# TeraDMX_v1_2.net
KiCad netlist of a schematic drawn in EAGLE
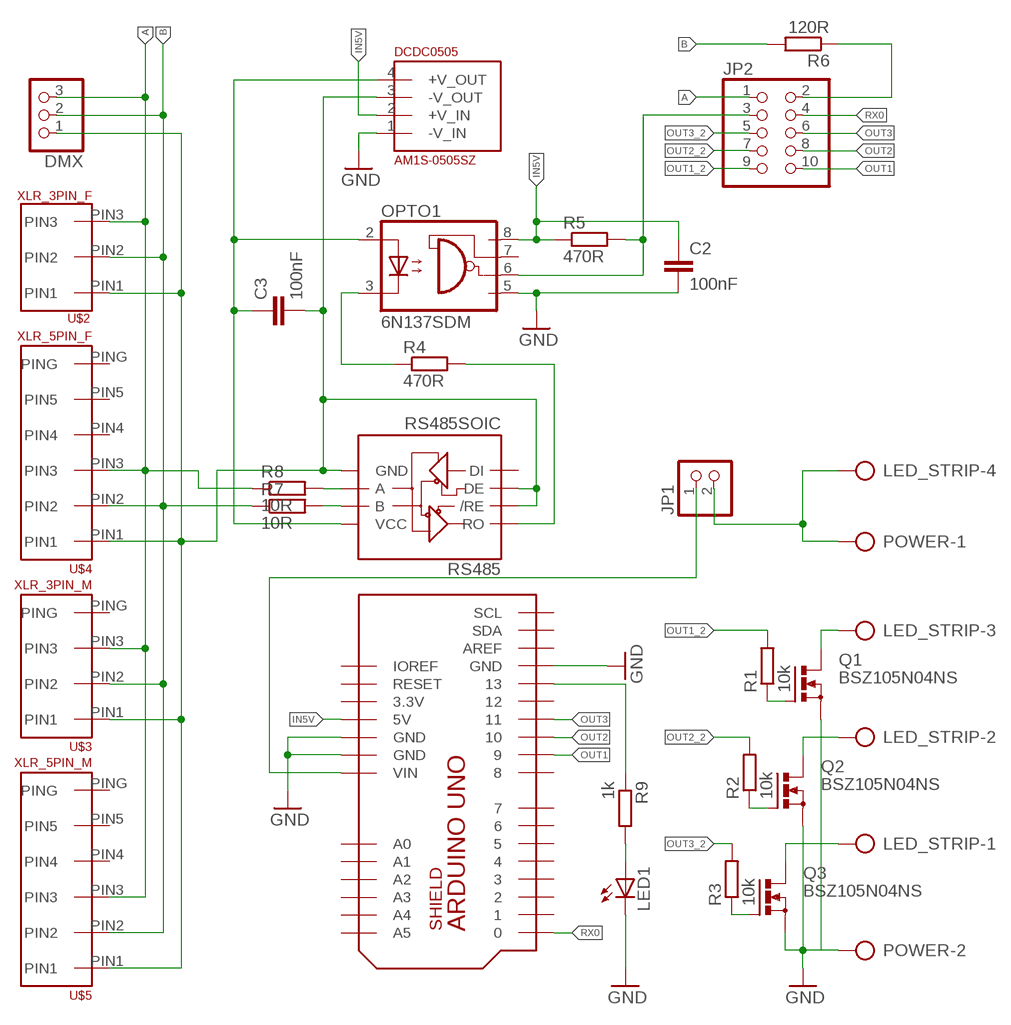
[diagram p0: schematic, sheet 1]

(export (version "E")
  (design (tool "Eeschema 10.0.6"))
  (components
    (comp (ref "C2")
      (value "100nF")
      (footprint "eagle-import:C0805")
      (libsource (lib "eagle-import") (part "C-EUC0805"))
    )
    (comp (ref "C3")
      (value "100nF")
      (footprint "eagle-import:C0805")
      (libsource (lib "eagle-import") (part "C-EUC0805"))
    )
    (comp (ref "DCDC0505")
      (value "AM1S-0505SZ")
      (footprint "eagle-import:AM1S-0505SZ")
      (libsource (lib "eagle-import") (part "AM1S-0505SZ"))
    )
    (comp (ref "DMX")
      (value "PINHD-1X3")
      (footprint "eagle-import:1X03")
      (libsource (lib "eagle-import") (part "PINHD-1X3"))
    )
    (comp (ref "JP1")
      (value "PINHD-1X2")
      (footprint "eagle-import:1X02")
      (libsource (lib "eagle-import") (part "PINHD-1X2"))
    )
    (comp (ref "JP2")
      (value "PINHD-2X5")
      (footprint "eagle-import:2X05")
      (libsource (lib "eagle-import") (part "PINHD-2X5"))
    )
    (comp (ref "LED1")
      (value "LEDCHIP-LED0805")
      (footprint "eagle-import:CHIP-LED0805")
      (libsource (lib "eagle-import") (part "LEDCHIP-LED0805"))
    )
    (comp (ref "LED_STRIP")
      (value "AK300/4")
      (footprint "eagle-import:AK300_4")
      (libsource (lib "eagle-import") (part "AK300/4"))
    )
    (comp (ref "OPTO1")
      (value "6N137SDM")
      (footprint "eagle-import:6N137SDM")
      (libsource (lib "eagle-import") (part "6N137SDM"))
    )
    (comp (ref "POWER")
      (value "AK300/2")
      (footprint "eagle-import:AK300_2")
      (libsource (lib "eagle-import") (part "AK300/2"))
    )
    (comp (ref "Q1")
      (value "BSZ105N04NS")
      (footprint "eagle-import:PG-TDSON-8")
      (libsource (lib "eagle-import") (part "BSZ105N04NS"))
    )
    (comp (ref "Q2")
      (value "BSZ105N04NS")
      (footprint "eagle-import:PG-TDSON-8")
      (libsource (lib "eagle-import") (part "BSZ105N04NS"))
    )
    (comp (ref "Q3")
      (value "BSZ105N04NS")
      (footprint "eagle-import:PG-TDSON-8")
      (libsource (lib "eagle-import") (part "BSZ105N04NS"))
    )
    (comp (ref "R1")
      (value "10k")
      (footprint "eagle-import:M0805")
      (libsource (lib "eagle-import") (part "R-EU_M0805"))
    )
    (comp (ref "R2")
      (value "10k")
      (footprint "eagle-import:M0805")
      (libsource (lib "eagle-import") (part "R-EU_M0805"))
    )
    (comp (ref "R3")
      (value "10k")
      (footprint "eagle-import:M0805")
      (libsource (lib "eagle-import") (part "R-EU_M0805"))
    )
    (comp (ref "R4")
      (value "470R")
      (footprint "eagle-import:M0805")
      (libsource (lib "eagle-import") (part "R-EU_M0805"))
    )
    (comp (ref "R5")
      (value "470R")
      (footprint "eagle-import:R0805")
      (libsource (lib "eagle-import") (part "R-EU_R0805"))
    )
    (comp (ref "R6")
      (value "120R")
      (footprint "eagle-import:M0805")
      (libsource (lib "eagle-import") (part "R-EU_M0805"))
    )
    (comp (ref "R7")
      (value "10R")
      (footprint "eagle-import:M0805")
      (libsource (lib "eagle-import") (part "R-EU_M0805"))
    )
    (comp (ref "R8")
      (value "10R")
      (footprint "eagle-import:M0805")
      (libsource (lib "eagle-import") (part "R-EU_M0805"))
    )
    (comp (ref "R9")
      (value "1k")
      (footprint "eagle-import:M0805")
      (libsource (lib "eagle-import") (part "R-EU_M0805"))
    )
    (comp (ref "RS485")
      (value "RS485SOIC")
      (footprint "eagle-import:SO08")
      (libsource (lib "eagle-import") (part "RS485SOIC"))
    )
    (comp (ref "U$2")
      (value "XLR_3PIN_F")
      (footprint "eagle-import:XLR_3PIN_F")
      (libsource (lib "eagle-import") (part "XLR_3PIN_F"))
    )
    (comp (ref "U$3")
      (value "XLR_3PIN_M")
      (footprint "eagle-import:XLR_3PIN_M")
      (libsource (lib "eagle-import") (part "XLR_3PIN_M"))
    )
    (comp (ref "U$4")
      (value "XLR_5PIN_F")
      (footprint "eagle-import:XLR_5PIN_F")
      (libsource (lib "eagle-import") (part "XLR_5PIN_F"))
    )
    (comp (ref "U$5")
      (value "XLR_5PIN_M")
      (footprint "eagle-import:XLR_5PIN_M")
      (libsource (lib "eagle-import") (part "XLR_5PIN_M"))
    )
    (comp (ref "U$6")
      (value "ARDUINO_UNO_SHIELD")
      (footprint "eagle-import:ARDUINO_UNO_SHIELD")
      (libsource (lib "eagle-import") (part "ARDUINO_UNO_SHIELD"))
    )
  )
  (nets
    (net (code "1") (name "/3.3V") (class "Default")
      (node (ref "U$6") (pin "3.3V") (pinfunction "3.3V_3.3V") (pintype "power_in"))
    )
    (net (code "2") (name "A") (class "Default")
      (node (ref "DMX") (pin "3") (pinfunction "3_3") (pintype "passive"))
      (node (ref "JP2") (pin "1") (pinfunction "1_1") (pintype "passive"))
      (node (ref "R8") (pin "1") (pinfunction "1_1") (pintype "passive"))
      (node (ref "U$2") (pin "PIN3") (pinfunction "PIN3_PIN3") (pintype "bidirectional"))
      (node (ref "U$3") (pin "PIN3") (pinfunction "PIN3_PIN3") (pintype "bidirectional"))
      (node (ref "U$4") (pin "PIN3") (pinfunction "PIN3_PIN3") (pintype "bidirectional"))
      (node (ref "U$5") (pin "PIN3") (pinfunction "PIN3_PIN3") (pintype "bidirectional"))
    )
    (net (code "3") (name "B") (class "Default")
      (node (ref "DMX") (pin "2") (pinfunction "2_2") (pintype "passive"))
      (node (ref "R6") (pin "2") (pinfunction "2_2") (pintype "passive"))
      (node (ref "R7") (pin "1") (pinfunction "1_1") (pintype "passive"))
      (node (ref "U$2") (pin "PIN2") (pinfunction "PIN2_PIN2") (pintype "bidirectional"))
      (node (ref "U$3") (pin "PIN2") (pinfunction "PIN2_PIN2") (pintype "bidirectional"))
      (node (ref "U$4") (pin "PIN2") (pinfunction "PIN2_PIN2") (pintype "bidirectional"))
      (node (ref "U$5") (pin "PIN2") (pinfunction "PIN2_PIN2") (pintype "bidirectional"))
    )
    (net (code "4") (name "GND") (class "Default")
      (node (ref "C2") (pin "2") (pinfunction "2_2") (pintype "passive"))
      (node (ref "DCDC0505") (pin "1") (pinfunction "-V_IN_1") (pintype "power_in"))
      (node (ref "LED1") (pin "C") (pinfunction "C_C") (pintype "passive"))
      (node (ref "OPTO1") (pin "5") (pinfunction "GND_5") (pintype "passive"))
      (node (ref "POWER") (pin "2") (pinfunction "KL_2") (pintype "passive"))
      (node (ref "Q1") (pin "1") (pinfunction "S_1") (pintype "passive"))
      (node (ref "Q1") (pin "2") (pinfunction "S_2") (pintype "passive"))
      (node (ref "Q1") (pin "3") (pinfunction "S_3") (pintype "passive"))
      (node (ref "Q2") (pin "1") (pinfunction "S_1") (pintype "passive"))
      (node (ref "Q2") (pin "2") (pinfunction "S_2") (pintype "passive"))
      (node (ref "Q2") (pin "3") (pinfunction "S_3") (pintype "passive"))
      (node (ref "Q3") (pin "1") (pinfunction "S_1") (pintype "passive"))
      (node (ref "Q3") (pin "2") (pinfunction "S_2") (pintype "passive"))
      (node (ref "Q3") (pin "3") (pinfunction "S_3") (pintype "passive"))
      (node (ref "U$6") (pin "GND1") (pinfunction "GND_GND1") (pintype "power_in"))
      (node (ref "U$6") (pin "GND2") (pinfunction "GND_GND2") (pintype "power_in"))
      (node (ref "U$6") (pin "GND3") (pinfunction "GND_GND3") (pintype "power_in"))
    )
    (net (code "5") (name "IN5V") (class "Default")
      (node (ref "C2") (pin "1") (pinfunction "1_1") (pintype "passive"))
      (node (ref "DCDC0505") (pin "2") (pinfunction "+V_IN_2") (pintype "power_in"))
      (node (ref "OPTO1") (pin "8") (pinfunction "VCC_8") (pintype "passive"))
      (node (ref "R5") (pin "1") (pinfunction "1_1") (pintype "passive"))
      (node (ref "U$6") (pin "5V") (pinfunction "5V_5V") (pintype "power_in"))
    )
    (net (code "6") (name "Net-(DCDC0505-+V_OUT)") (class "Default")
      (node (ref "C3") (pin "1") (pinfunction "1_1") (pintype "passive"))
      (node (ref "DCDC0505") (pin "4") (pinfunction "+V_OUT_4") (pintype "power_in"))
      (node (ref "OPTO1") (pin "2") (pinfunction "A_2") (pintype "passive"))
      (node (ref "RS485") (pin "8") (pinfunction "VCC_8") (pintype "bidirectional"))
    )
    (net (code "7") (name "Net-(DCDC0505--V_OUT)") (class "Default")
      (node (ref "C3") (pin "2") (pinfunction "2_2") (pintype "passive"))
      (node (ref "DCDC0505") (pin "3") (pinfunction "-V_OUT_3") (pintype "power_in"))
      (node (ref "DMX") (pin "1") (pinfunction "1_1") (pintype "passive"))
      (node (ref "RS485") (pin "2") (pinfunction "/RE_2") (pintype "bidirectional"))
      (node (ref "RS485") (pin "3") (pinfunction "DE_3") (pintype "bidirectional"))
      (node (ref "RS485") (pin "5") (pinfunction "GND_5") (pintype "bidirectional"))
      (node (ref "U$2") (pin "PIN1") (pinfunction "PIN1_PIN1") (pintype "bidirectional"))
      (node (ref "U$3") (pin "PIN1") (pinfunction "PIN1_PIN1") (pintype "bidirectional"))
      (node (ref "U$4") (pin "PIN1") (pinfunction "PIN1_PIN1") (pintype "bidirectional"))
      (node (ref "U$5") (pin "PIN1") (pinfunction "PIN1_PIN1") (pintype "bidirectional"))
    )
    (net (code "8") (name "Net-(JP1-Pad1)") (class "Default")
      (node (ref "JP1") (pin "1") (pinfunction "1_1") (pintype "passive"))
      (node (ref "U$6") (pin "VIN") (pinfunction "VIN_VIN") (pintype "power_in"))
    )
    (net (code "9") (name "Net-(JP2-Pad2)") (class "Default")
      (node (ref "JP2") (pin "2") (pinfunction "2_2") (pintype "passive"))
      (node (ref "R6") (pin "1") (pinfunction "1_1") (pintype "passive"))
    )
    (net (code "10") (name "Net-(LED1-PadA)") (class "Default")
      (node (ref "LED1") (pin "A") (pinfunction "A_A") (pintype "passive"))
      (node (ref "R9") (pin "2") (pinfunction "2_2") (pintype "passive"))
    )
    (net (code "11") (name "Net-(LED_STRIPA-KL)") (class "Default")
      (node (ref "LED_STRIP") (pin "1") (pinfunction "KL_1") (pintype "passive"))
      (node (ref "Q3") (pin "5") (pinfunction "D_5") (pintype "passive"))
      (node (ref "Q3") (pin "6") (pinfunction "D_6") (pintype "passive"))
      (node (ref "Q3") (pin "7") (pinfunction "D_7") (pintype "passive"))
      (node (ref "Q3") (pin "8") (pinfunction "D_8") (pintype "passive"))
      (node (ref "Q3") (pin "TH") (pinfunction "D_TH") (pintype "passive"))
    )
    (net (code "12") (name "Net-(LED_STRIPB-KL)") (class "Default")
      (node (ref "LED_STRIP") (pin "2") (pinfunction "KL_2") (pintype "passive"))
      (node (ref "Q2") (pin "5") (pinfunction "D_5") (pintype "passive"))
      (node (ref "Q2") (pin "6") (pinfunction "D_6") (pintype "passive"))
      (node (ref "Q2") (pin "7") (pinfunction "D_7") (pintype "passive"))
      (node (ref "Q2") (pin "8") (pinfunction "D_8") (pintype "passive"))
      (node (ref "Q2") (pin "TH") (pinfunction "D_TH") (pintype "passive"))
    )
    (net (code "13") (name "Net-(LED_STRIPC-KL)") (class "Default")
      (node (ref "LED_STRIP") (pin "3") (pinfunction "KL_3") (pintype "passive"))
      (node (ref "Q1") (pin "5") (pinfunction "D_5") (pintype "passive"))
      (node (ref "Q1") (pin "6") (pinfunction "D_6") (pintype "passive"))
      (node (ref "Q1") (pin "7") (pinfunction "D_7") (pintype "passive"))
      (node (ref "Q1") (pin "8") (pinfunction "D_8") (pintype "passive"))
      (node (ref "Q1") (pin "TH") (pinfunction "D_TH") (pintype "passive"))
    )
    (net (code "14") (name "Net-(LED_STRIPD-KL)") (class "Default")
      (node (ref "JP1") (pin "2") (pinfunction "2_2") (pintype "passive"))
      (node (ref "LED_STRIP") (pin "4") (pinfunction "KL_4") (pintype "passive"))
      (node (ref "POWER") (pin "1") (pinfunction "KL_1") (pintype "passive"))
    )
    (net (code "15") (name "Net-(OPTO1-C)") (class "Default")
      (node (ref "OPTO1") (pin "3") (pinfunction "C_3") (pintype "passive"))
      (node (ref "R4") (pin "1") (pinfunction "1_1") (pintype "passive"))
    )
    (net (code "16") (name "Net-(OPTO1-VO)") (class "Default")
      (node (ref "JP2") (pin "3") (pinfunction "3_3") (pintype "passive"))
      (node (ref "OPTO1") (pin "6") (pinfunction "VO_6") (pintype "passive"))
      (node (ref "R5") (pin "2") (pinfunction "2_2") (pintype "passive"))
    )
    (net (code "17") (name "Net-(Q1-G)") (class "Default")
      (node (ref "Q1") (pin "4") (pinfunction "G_4") (pintype "passive"))
      (node (ref "R1") (pin "1") (pinfunction "1_1") (pintype "passive"))
    )
    (net (code "18") (name "Net-(Q2-G)") (class "Default")
      (node (ref "Q2") (pin "4") (pinfunction "G_4") (pintype "passive"))
      (node (ref "R2") (pin "1") (pinfunction "1_1") (pintype "passive"))
    )
    (net (code "19") (name "Net-(Q3-G)") (class "Default")
      (node (ref "Q3") (pin "4") (pinfunction "G_4") (pintype "passive"))
      (node (ref "R3") (pin "1") (pinfunction "1_1") (pintype "passive"))
    )
    (net (code "20") (name "Net-(R9-Pad1)") (class "Default")
      (node (ref "R9") (pin "1") (pinfunction "1_1") (pintype "passive"))
      (node (ref "U$6") (pin "13") (pinfunction "13_13") (pintype "bidirectional"))
    )
    (net (code "21") (name "Net-(RS485-A)") (class "Default")
      (node (ref "R8") (pin "2") (pinfunction "2_2") (pintype "passive"))
      (node (ref "RS485") (pin "6") (pinfunction "A_6") (pintype "bidirectional"))
    )
    (net (code "22") (name "Net-(RS485-B)") (class "Default")
      (node (ref "R7") (pin "2") (pinfunction "2_2") (pintype "passive"))
      (node (ref "RS485") (pin "7") (pinfunction "B_7") (pintype "bidirectional"))
    )
    (net (code "23") (name "Net-(RS485-RO)") (class "Default")
      (node (ref "R4") (pin "2") (pinfunction "2_2") (pintype "passive"))
      (node (ref "RS485") (pin "1") (pinfunction "RO_1") (pintype "bidirectional"))
    )
    (net (code "24") (name "OUT1") (class "Default")
      (node (ref "JP2") (pin "10") (pinfunction "10_10") (pintype "passive"))
      (node (ref "U$6") (pin "9") (pinfunction "9_9") (pintype "bidirectional"))
    )
    (net (code "25") (name "OUT1_2") (class "Default")
      (node (ref "JP2") (pin "9") (pinfunction "9_9") (pintype "passive"))
      (node (ref "R1") (pin "2") (pinfunction "2_2") (pintype "passive"))
    )
    (net (code "26") (name "OUT2") (class "Default")
      (node (ref "JP2") (pin "8") (pinfunction "8_8") (pintype "passive"))
      (node (ref "U$6") (pin "10") (pinfunction "10_10") (pintype "bidirectional"))
    )
    (net (code "27") (name "OUT2_2") (class "Default")
      (node (ref "JP2") (pin "7") (pinfunction "7_7") (pintype "passive"))
      (node (ref "R2") (pin "2") (pinfunction "2_2") (pintype "passive"))
    )
    (net (code "28") (name "OUT3") (class "Default")
      (node (ref "JP2") (pin "6") (pinfunction "6_6") (pintype "passive"))
      (node (ref "U$6") (pin "11") (pinfunction "11_11") (pintype "bidirectional"))
    )
    (net (code "29") (name "OUT3_2") (class "Default")
      (node (ref "JP2") (pin "5") (pinfunction "5_5") (pintype "passive"))
      (node (ref "R3") (pin "2") (pinfunction "2_2") (pintype "passive"))
    )
    (net (code "30") (name "RX0") (class "Default")
      (node (ref "JP2") (pin "4") (pinfunction "4_4") (pintype "passive"))
      (node (ref "U$6") (pin "0") (pinfunction "0_0") (pintype "bidirectional"))
    )
    (net (code "31") (name "unconnected-(OPTO1-VE-Pad7)") (class "Default")
      (node (ref "OPTO1") (pin "7") (pinfunction "VE_7") (pintype "passive"))
    )
    (net (code "32") (name "unconnected-(RS485-DI-Pad4)") (class "Default")
      (node (ref "RS485") (pin "4") (pinfunction "DI_4") (pintype "bidirectional"))
    )
    (net (code "33") (name "unconnected-(U$3-PadPING)") (class "Default")
      (node (ref "U$3") (pin "PING") (pinfunction "PING_PING") (pintype "bidirectional"))
    )
    (net (code "34") (name "unconnected-(U$4-PadPIN4)") (class "Default")
      (node (ref "U$4") (pin "PIN4") (pinfunction "PIN4_PIN4") (pintype "bidirectional"))
    )
    (net (code "35") (name "unconnected-(U$4-PadPIN5)") (class "Default")
      (node (ref "U$4") (pin "PIN5") (pinfunction "PIN5_PIN5") (pintype "bidirectional"))
    )
    (net (code "36") (name "unconnected-(U$4-PadPING)") (class "Default")
      (node (ref "U$4") (pin "PING") (pinfunction "PING_PING") (pintype "bidirectional"))
    )
    (net (code "37") (name "unconnected-(U$5-PadPIN4)") (class "Default")
      (node (ref "U$5") (pin "PIN4") (pinfunction "PIN4_PIN4") (pintype "bidirectional"))
    )
    (net (code "38") (name "unconnected-(U$5-PadPIN5)") (class "Default")
      (node (ref "U$5") (pin "PIN5") (pinfunction "PIN5_PIN5") (pintype "bidirectional"))
    )
    (net (code "39") (name "unconnected-(U$5-PadPING)") (class "Default")
      (node (ref "U$5") (pin "PING") (pinfunction "PING_PING") (pintype "bidirectional"))
    )
    (net (code "40") (name "unconnected-(U$6-Pad1)") (class "Default")
      (node (ref "U$6") (pin "1") (pinfunction "1_1") (pintype "bidirectional"))
    )
    (net (code "41") (name "unconnected-(U$6-Pad2)") (class "Default")
      (node (ref "U$6") (pin "2") (pinfunction "2_2") (pintype "bidirectional"))
    )
    (net (code "42") (name "unconnected-(U$6-Pad3)") (class "Default")
      (node (ref "U$6") (pin "3") (pinfunction "3_3") (pintype "bidirectional"))
    )
    (net (code "43") (name "unconnected-(U$6-Pad4)") (class "Default")
      (node (ref "U$6") (pin "4") (pinfunction "4_4") (pintype "bidirectional"))
    )
    (net (code "44") (name "unconnected-(U$6-Pad5)") (class "Default")
      (node (ref "U$6") (pin "5") (pinfunction "5_5") (pintype "bidirectional"))
    )
    (net (code "45") (name "unconnected-(U$6-Pad6)") (class "Default")
      (node (ref "U$6") (pin "6") (pinfunction "6_6") (pintype "bidirectional"))
    )
    (net (code "46") (name "unconnected-(U$6-Pad7)") (class "Default")
      (node (ref "U$6") (pin "7") (pinfunction "7_7") (pintype "bidirectional"))
    )
    (net (code "47") (name "unconnected-(U$6-Pad8)") (class "Default")
      (node (ref "U$6") (pin "8") (pinfunction "8_8") (pintype "bidirectional"))
    )
    (net (code "48") (name "unconnected-(U$6-Pad12)") (class "Default")
      (node (ref "U$6") (pin "12") (pinfunction "12_12") (pintype "bidirectional"))
    )
    (net (code "49") (name "unconnected-(U$6-PadA0)") (class "Default")
      (node (ref "U$6") (pin "A0") (pinfunction "A0_A0") (pintype "bidirectional"))
    )
    (net (code "50") (name "unconnected-(U$6-PadA1)") (class "Default")
      (node (ref "U$6") (pin "A1") (pinfunction "A1_A1") (pintype "bidirectional"))
    )
    (net (code "51") (name "unconnected-(U$6-PadA2)") (class "Default")
      (node (ref "U$6") (pin "A2") (pinfunction "A2_A2") (pintype "bidirectional"))
    )
    (net (code "52") (name "unconnected-(U$6-PadA3)") (class "Default")
      (node (ref "U$6") (pin "A3") (pinfunction "A3_A3") (pintype "bidirectional"))
    )
    (net (code "53") (name "unconnected-(U$6-PadA4)") (class "Default")
      (node (ref "U$6") (pin "A4") (pinfunction "A4_A4") (pintype "bidirectional"))
    )
    (net (code "54") (name "unconnected-(U$6-PadA5)") (class "Default")
      (node (ref "U$6") (pin "A5") (pinfunction "A5_A5") (pintype "bidirectional"))
    )
    (net (code "55") (name "unconnected-(U$6-PadAREF)") (class "Default")
      (node (ref "U$6") (pin "AREF") (pinfunction "AREF_AREF") (pintype "input"))
    )
    (net (code "56") (name "unconnected-(U$6-PadIOREF)") (class "Default")
      (node (ref "U$6") (pin "IOREF") (pinfunction "IOREF_IOREF") (pintype "input"))
    )
    (net (code "57") (name "unconnected-(U$6-PadRESET)") (class "Default")
      (node (ref "U$6") (pin "RESET") (pinfunction "RESET_RESET") (pintype "bidirectional"))
    )
    (net (code "58") (name "unconnected-(U$6-PadSCL)") (class "Default")
      (node (ref "U$6") (pin "SCL") (pinfunction "SCL_SCL") (pintype "bidirectional"))
    )
    (net (code "59") (name "unconnected-(U$6-PadSDA)") (class "Default")
      (node (ref "U$6") (pin "SDA") (pinfunction "SDA_SDA") (pintype "bidirectional"))
    )
  )
)
